# Sheet1.net
KiCad netlist of a schematic drawn in Altium Designer
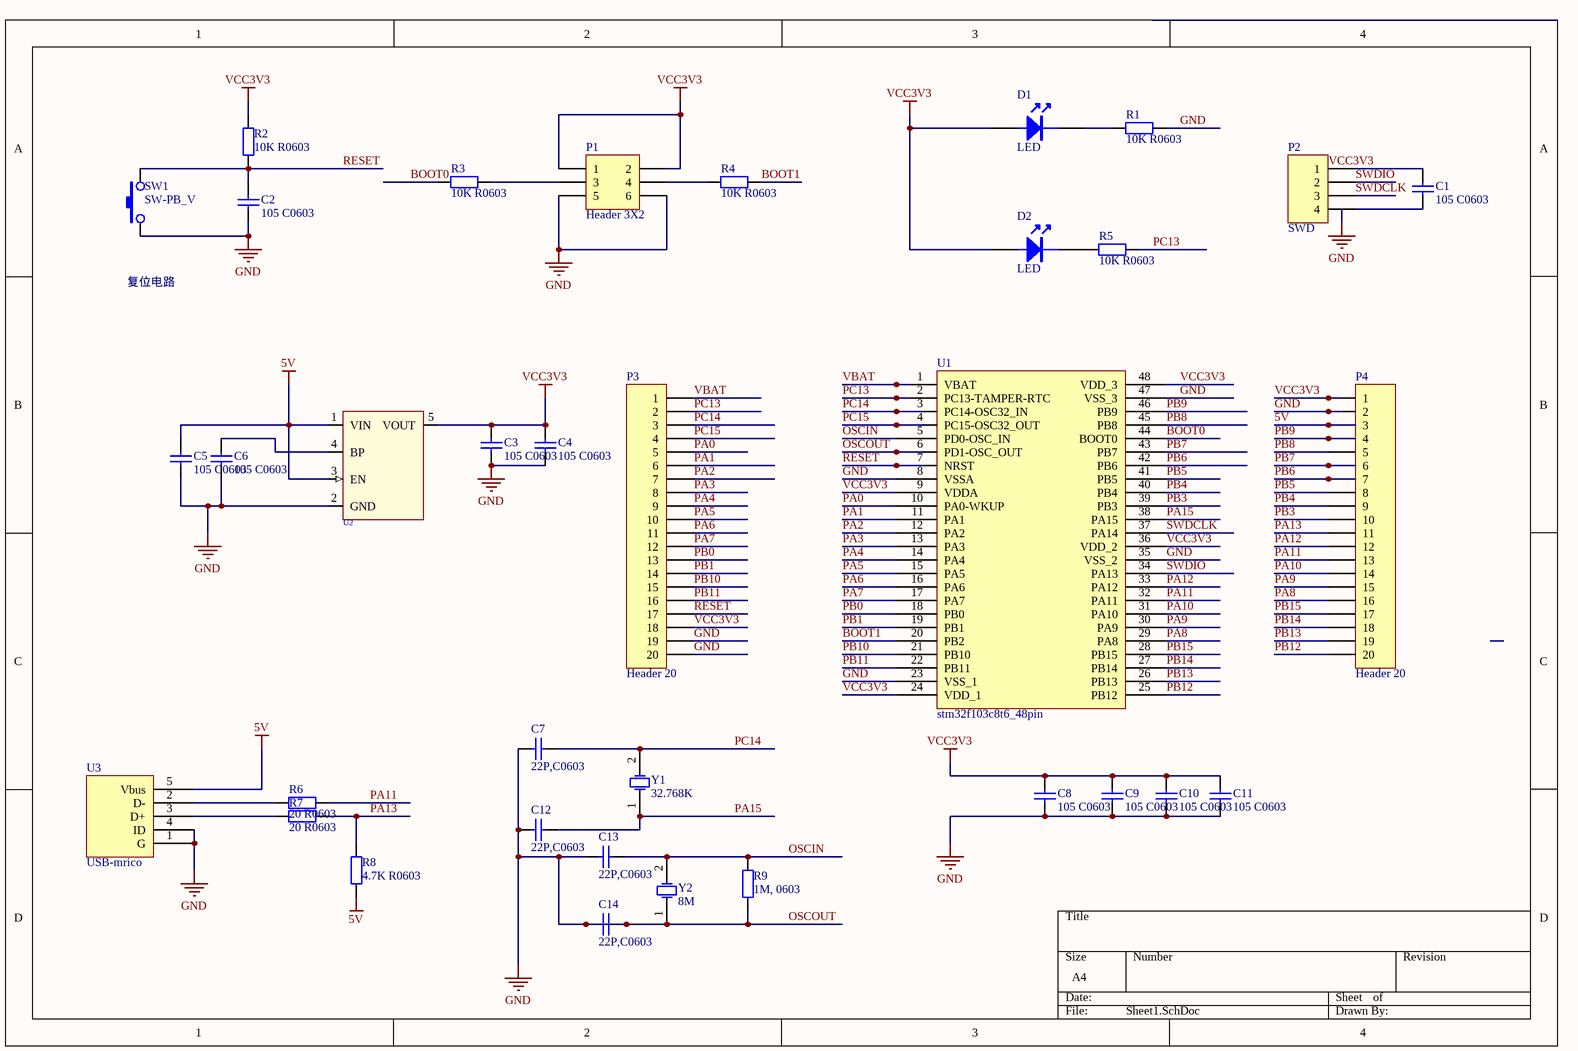
[diagram p0: Sheet1.SchDoc]

(export (version "E")
  (design (tool "Eeschema 10.0.6"))
  (components
    (comp (ref "C1")
      (value "105 C0603")
      (footprint "C 0603")
      (fields (field (name "PUBLISHER") "Altium Limited"))
      (libsource (lib "stm32原理图库") (part "Cap"))
    )
    (comp (ref "C2")
      (value "105 C0603")
      (footprint "C 0603")
      (fields (field (name "PUBLISHER") "Altium Limited"))
      (libsource (lib "stm32原理图库") (part "Cap"))
    )
    (comp (ref "C3")
      (value "105 C0603")
      (footprint "C 0603")
      (fields (field (name "PUBLISHER") "Altium Limited"))
      (libsource (lib "stm32原理图库") (part "Cap"))
    )
    (comp (ref "C4")
      (value "105 C0603")
      (footprint "C 0603")
      (fields (field (name "PUBLISHER") "Altium Limited"))
      (libsource (lib "stm32原理图库") (part "Cap"))
    )
    (comp (ref "C5")
      (value "105 C0603")
      (footprint "C 0603")
      (fields (field (name "PUBLISHER") "Altium Limited"))
      (libsource (lib "stm32原理图库") (part "Cap"))
    )
    (comp (ref "C6")
      (value "105 C0603")
      (footprint "C 0603")
      (fields (field (name "PUBLISHER") "Altium Limited"))
      (libsource (lib "stm32原理图库") (part "Cap"))
    )
    (comp (ref "C7")
      (value "22P,C0603")
      (footprint "C 0603")
      (fields (field (name "PUBLISHER") "Altium Limited"))
      (libsource (lib "stm32原理图库") (part "Cap"))
    )
    (comp (ref "C8")
      (value "105 C0603")
      (footprint "C 0603")
      (fields (field (name "PUBLISHER") "Altium Limited"))
      (libsource (lib "stm32原理图库") (part "Cap"))
    )
    (comp (ref "C9")
      (value "105 C0603")
      (footprint "C 0603")
      (fields (field (name "PUBLISHER") "Altium Limited"))
      (libsource (lib "stm32原理图库") (part "Cap"))
    )
    (comp (ref "C10")
      (value "105 C0603")
      (footprint "C 0603")
      (fields (field (name "PUBLISHER") "Altium Limited"))
      (libsource (lib "stm32原理图库") (part "Cap"))
    )
    (comp (ref "C11")
      (value "105 C0603")
      (footprint "C 0603")
      (fields (field (name "PUBLISHER") "Altium Limited"))
      (libsource (lib "stm32原理图库") (part "Cap"))
    )
    (comp (ref "C12")
      (value "22P,C0603")
      (footprint "C 0603")
      (fields (field (name "PUBLISHER") "Altium Limited"))
      (libsource (lib "stm32原理图库") (part "Cap"))
    )
    (comp (ref "C13")
      (value "22P,C0603")
      (footprint "C 0603")
      (fields (field (name "PUBLISHER") "Altium Limited"))
      (libsource (lib "stm32原理图库") (part "Cap"))
    )
    (comp (ref "C14")
      (value "22P,C0603")
      (footprint "C 0603")
      (fields (field (name "PUBLISHER") "Altium Limited"))
      (libsource (lib "stm32原理图库") (part "Cap"))
    )
    (comp (ref "D1") (value "LED") (footprint "LED 0805G") (libsource (lib "stm32原理图库") (part "LED")))
    (comp (ref "D2") (value "LED") (footprint "LED 0805G") (libsource (lib "stm32原理图库") (part "LED")))
    (comp (ref "P1")
      (value "Header 3X2")
      (footprint "HDR-3X2")
      (fields (field (name "PUBLISHER") "Altium Limited"))
      (libsource (lib "stm32原理图库") (part "Header 2*3"))
    )
    (comp (ref "P2")
      (value "SWD")
      (footprint "HDR-1X4_H")
      (fields (field (name "PUBLISHER") "Altium Limited"))
      (libsource (lib "stm32原理图库") (part "Header 1*4"))
    )
    (comp (ref "P3")
      (value "Header 20")
      (footprint "HDR1X20")
      (fields (field (name "PUBLISHER") "Altium Limited"))
      (libsource (lib "") (part "Header1* 20_1"))
    )
    (comp (ref "P4")
      (value "Header 20")
      (footprint "HDR1X20")
      (fields (field (name "PUBLISHER") "Altium Limited"))
      (libsource (lib "stm32原理图库") (part "Header1* 20"))
    )
    (comp (ref "R1")
      (value "10K R0603")
      (footprint "R 0603")
      (fields (field (name "PUBLISHER") "Altium Limited"))
      (libsource (lib "") (part "Res2_3"))
    )
    (comp (ref "R2")
      (value "10K R0603")
      (footprint "R 0603")
      (fields (field (name "PUBLISHER") "Altium Limited"))
      (libsource (lib "") (part "Res2_2"))
    )
    (comp (ref "R3")
      (value "10K R0603")
      (footprint "R 0603")
      (fields (field (name "PUBLISHER") "Altium Limited"))
      (libsource (lib "stm32原理图库") (part "Res2"))
    )
    (comp (ref "R4")
      (value "10K R0603")
      (footprint "R 0603")
      (fields (field (name "PUBLISHER") "Altium Limited"))
      (libsource (lib "stm32原理图库") (part "Res2"))
    )
    (comp (ref "R5")
      (value "10K R0603")
      (footprint "R 0603")
      (fields (field (name "PUBLISHER") "Altium Limited"))
      (libsource (lib "") (part "Res2_3"))
    )
    (comp (ref "R6")
      (value "20 R0603")
      (footprint "R 0603")
      (fields (field (name "PUBLISHER") "Altium Limited"))
      (libsource (lib "stm32原理图库") (part "Res2"))
    )
    (comp (ref "R7")
      (value "20 R0603")
      (footprint "R 0603")
      (fields (field (name "PUBLISHER") "Altium Limited"))
      (libsource (lib "stm32原理图库") (part "Res2"))
    )
    (comp (ref "R8")
      (value "4.7K R0603")
      (footprint "R 0603")
      (fields (field (name "PUBLISHER") "Altium Limited"))
      (libsource (lib "") (part "Res2_1"))
    )
    (comp (ref "R9")
      (value "1M, 0603")
      (footprint "R 0603")
      (fields (field (name "PUBLISHER") "Altium Limited"))
      (libsource (lib "") (part "Res2_1"))
    )
    (comp (ref "SW1")
      (value "SW-PB_V")
      (footprint "TSW SMD-3*6*2.5")
      (libsource (lib "stm32原理图库") (part "SW-PB_V"))
    )
    (comp (ref "U1")
      (value "stm32f103c8t6_48pin")
      (footprint "TQFP48 7x7_L")
      (libsource (lib "stm32原理图库") (part "stm32f103c8t6_48pin"))
    )
    (comp (ref "U2")
      (value "RT9193")
      (footprint "SOT23-5L")
      (fields (field (name "ICA_PARTNUM") "$$2191094$$RT9193-15CU5") (field (name "PART NUMBER") "TMP-13"))
      (libsource (lib "stm32原理图库") (part "RT9193X_5P"))
    )
    (comp (ref "U3")
      (value "USB-mrico")
      (footprint "USB-micro_B")
      (libsource (lib "stm32原理图库") (part "usb-STM"))
    )
    (comp (ref "Y1")
      (value "32.768K")
      (footprint "XTAL-49S DIP")
      (fields (field (name "PUBLISHER") "Altium Limited"))
      (libsource (lib "stm32原理图库") (part "XTAL"))
    )
    (comp (ref "Y2")
      (value "8M")
      (footprint "XTAL-49S DIP")
      (fields (field (name "PUBLISHER") "Altium Limited"))
      (libsource (lib "stm32原理图库") (part "XTAL"))
    )
  )
  (nets
    (net (code "1") (name "/BOOT0") (class "Default")
      (node (ref "R3") (pin "2") (pinfunction "2_2") (pintype "passive"))
      (node (ref "U1") (pin "44") (pinfunction "BOOT0_44") (pintype "passive"))
    )
    (net (code "2") (name "/BOOT1") (class "Default")
      (node (ref "R4") (pin "1") (pinfunction "1_1") (pintype "passive"))
      (node (ref "U1") (pin "20") (pinfunction "PB2_20") (pintype "passive"))
    )
    (net (code "3") (name "/OSCIN") (class "Default")
      (node (ref "C13") (pin "1") (pinfunction "1_1") (pintype "passive"))
      (node (ref "R9") (pin "1") (pinfunction "1_1") (pintype "passive"))
      (node (ref "U1") (pin "5") (pinfunction "PD0-OSC_IN_5") (pintype "passive"))
      (node (ref "Y2") (pin "2") (pinfunction "OSC2_2") (pintype "passive"))
    )
    (net (code "4") (name "/PA0") (class "Default")
      (node (ref "P3") (pin "5") (pinfunction "5_5") (pintype "passive"))
      (node (ref "U1") (pin "10") (pinfunction "PA0-WKUP_10") (pintype "passive"))
    )
    (net (code "5") (name "/PA1") (class "Default")
      (node (ref "P3") (pin "6") (pinfunction "6_6") (pintype "passive"))
      (node (ref "U1") (pin "11") (pinfunction "PA1_11") (pintype "passive"))
    )
    (net (code "6") (name "/PA2") (class "Default")
      (node (ref "P3") (pin "7") (pinfunction "7_7") (pintype "passive"))
      (node (ref "U1") (pin "12") (pinfunction "PA2_12") (pintype "passive"))
    )
    (net (code "7") (name "/PA3") (class "Default")
      (node (ref "P3") (pin "8") (pinfunction "8_8") (pintype "passive"))
      (node (ref "U1") (pin "13") (pinfunction "PA3_13") (pintype "passive"))
    )
    (net (code "8") (name "/PA4") (class "Default")
      (node (ref "P3") (pin "9") (pinfunction "9_9") (pintype "passive"))
      (node (ref "U1") (pin "14") (pinfunction "PA4_14") (pintype "passive"))
    )
    (net (code "9") (name "/PA5") (class "Default")
      (node (ref "P3") (pin "10") (pinfunction "10_10") (pintype "passive"))
      (node (ref "U1") (pin "15") (pinfunction "PA5_15") (pintype "passive"))
    )
    (net (code "10") (name "/PA6") (class "Default")
      (node (ref "P3") (pin "11") (pinfunction "11_11") (pintype "passive"))
      (node (ref "U1") (pin "16") (pinfunction "PA6_16") (pintype "passive"))
    )
    (net (code "11") (name "/PA7") (class "Default")
      (node (ref "P3") (pin "12") (pinfunction "12_12") (pintype "passive"))
      (node (ref "U1") (pin "17") (pinfunction "PA7_17") (pintype "passive"))
    )
    (net (code "12") (name "/PA8") (class "Default")
      (node (ref "P4") (pin "16") (pinfunction "16_16") (pintype "passive"))
      (node (ref "U1") (pin "29") (pinfunction "PA8_29") (pintype "passive"))
    )
    (net (code "13") (name "/PA9") (class "Default")
      (node (ref "P4") (pin "15") (pinfunction "15_15") (pintype "passive"))
      (node (ref "U1") (pin "30") (pinfunction "PA9_30") (pintype "passive"))
    )
    (net (code "14") (name "/PA10") (class "Default")
      (node (ref "P4") (pin "14") (pinfunction "14_14") (pintype "passive"))
      (node (ref "U1") (pin "31") (pinfunction "PA10_31") (pintype "passive"))
    )
    (net (code "15") (name "/PA11") (class "Default")
      (node (ref "P4") (pin "13") (pinfunction "13_13") (pintype "passive"))
      (node (ref "R6") (pin "1") (pinfunction "1_1") (pintype "passive"))
      (node (ref "U1") (pin "32") (pinfunction "PA11_32") (pintype "passive"))
    )
    (net (code "16") (name "/PA12") (class "Default")
      (node (ref "P4") (pin "12") (pinfunction "12_12") (pintype "passive"))
      (node (ref "U1") (pin "33") (pinfunction "PA12_33") (pintype "passive"))
    )
    (net (code "17") (name "/PA13") (class "Default")
      (node (ref "P4") (pin "11") (pinfunction "11_11") (pintype "passive"))
      (node (ref "R7") (pin "1") (pinfunction "1_1") (pintype "passive"))
      (node (ref "R8") (pin "1") (pinfunction "1_1") (pintype "passive"))
    )
    (net (code "18") (name "/PA15") (class "Default")
      (node (ref "C12") (pin "1") (pinfunction "1_1") (pintype "passive"))
      (node (ref "U1") (pin "38") (pinfunction "PA15_38") (pintype "passive"))
      (node (ref "Y1") (pin "1") (pinfunction "OSC1_1") (pintype "passive"))
    )
    (net (code "19") (name "/PB0") (class "Default")
      (node (ref "P3") (pin "13") (pinfunction "13_13") (pintype "passive"))
      (node (ref "U1") (pin "18") (pinfunction "PB0_18") (pintype "passive"))
    )
    (net (code "20") (name "/PB1") (class "Default")
      (node (ref "P3") (pin "14") (pinfunction "14_14") (pintype "passive"))
      (node (ref "U1") (pin "19") (pinfunction "PB1_19") (pintype "passive"))
    )
    (net (code "21") (name "/PB3") (class "Default")
      (node (ref "P4") (pin "10") (pinfunction "10_10") (pintype "passive"))
      (node (ref "U1") (pin "39") (pinfunction "PB3_39") (pintype "passive"))
    )
    (net (code "22") (name "/PB4") (class "Default")
      (node (ref "P4") (pin "9") (pinfunction "9_9") (pintype "passive"))
      (node (ref "U1") (pin "40") (pinfunction "PB4_40") (pintype "passive"))
    )
    (net (code "23") (name "/PB5") (class "Default")
      (node (ref "P4") (pin "8") (pinfunction "8_8") (pintype "passive"))
      (node (ref "U1") (pin "41") (pinfunction "PB5_41") (pintype "passive"))
    )
    (net (code "24") (name "/PB6") (class "Default")
      (node (ref "P4") (pin "7") (pinfunction "7_7") (pintype "passive"))
      (node (ref "U1") (pin "42") (pinfunction "PB6_42") (pintype "passive"))
    )
    (net (code "25") (name "/PB7") (class "Default")
      (node (ref "P4") (pin "6") (pinfunction "6_6") (pintype "passive"))
      (node (ref "U1") (pin "43") (pinfunction "PB7_43") (pintype "passive"))
    )
    (net (code "26") (name "/PB8") (class "Default")
      (node (ref "P4") (pin "5") (pinfunction "5_5") (pintype "passive"))
      (node (ref "U1") (pin "45") (pinfunction "PB8_45") (pintype "passive"))
    )
    (net (code "27") (name "/PB9") (class "Default")
      (node (ref "P4") (pin "4") (pinfunction "4_4") (pintype "passive"))
      (node (ref "U1") (pin "46") (pinfunction "PB9_46") (pintype "passive"))
    )
    (net (code "28") (name "/PB10") (class "Default")
      (node (ref "P3") (pin "15") (pinfunction "15_15") (pintype "passive"))
      (node (ref "U1") (pin "21") (pinfunction "PB10_21") (pintype "passive"))
    )
    (net (code "29") (name "/PB11") (class "Default")
      (node (ref "P3") (pin "16") (pinfunction "16_16") (pintype "passive"))
      (node (ref "U1") (pin "22") (pinfunction "PB11_22") (pintype "passive"))
    )
    (net (code "30") (name "/PB12") (class "Default")
      (node (ref "P4") (pin "20") (pinfunction "20_20") (pintype "passive"))
      (node (ref "U1") (pin "25") (pinfunction "PB12_25") (pintype "passive"))
    )
    (net (code "31") (name "/PB13") (class "Default")
      (node (ref "P4") (pin "19") (pinfunction "19_19") (pintype "passive"))
      (node (ref "U1") (pin "26") (pinfunction "PB13_26") (pintype "passive"))
    )
    (net (code "32") (name "/PB14") (class "Default")
      (node (ref "P4") (pin "18") (pinfunction "18_18") (pintype "passive"))
      (node (ref "U1") (pin "27") (pinfunction "PB14_27") (pintype "passive"))
    )
    (net (code "33") (name "/PB15") (class "Default")
      (node (ref "P4") (pin "17") (pinfunction "17_17") (pintype "passive"))
      (node (ref "U1") (pin "28") (pinfunction "PB15_28") (pintype "passive"))
    )
    (net (code "34") (name "/PC13") (class "Default")
      (node (ref "P3") (pin "2") (pinfunction "2_2") (pintype "passive"))
      (node (ref "R5") (pin "2") (pinfunction "2_2") (pintype "passive"))
      (node (ref "U1") (pin "2") (pinfunction "PC13-TAMPER-RTC_2") (pintype "passive"))
    )
    (net (code "35") (name "/PC14") (class "Default")
      (node (ref "C7") (pin "1") (pinfunction "1_1") (pintype "passive"))
      (node (ref "P3") (pin "3") (pinfunction "3_3") (pintype "passive"))
      (node (ref "U1") (pin "3") (pinfunction "PC14-OSC32_IN_3") (pintype "passive"))
      (node (ref "Y1") (pin "2") (pinfunction "OSC2_2") (pintype "passive"))
    )
    (net (code "36") (name "/PC15") (class "Default")
      (node (ref "P3") (pin "4") (pinfunction "4_4") (pintype "passive"))
      (node (ref "U1") (pin "4") (pinfunction "PC15-OSC32_OUT_4") (pintype "passive"))
    )
    (net (code "37") (name "/RESET") (class "Default")
      (node (ref "C2") (pin "2") (pinfunction "2_2") (pintype "passive"))
      (node (ref "P3") (pin "17") (pinfunction "17_17") (pintype "passive"))
      (node (ref "R2") (pin "1") (pinfunction "1_1") (pintype "passive"))
      (node (ref "SW1") (pin "2") (pinfunction "2_2") (pintype "passive"))
      (node (ref "U1") (pin "7") (pinfunction "NRST_7") (pintype "passive"))
    )
    (net (code "38") (name "/SWDCLK") (class "Default")
      (node (ref "P2") (pin "3") (pinfunction "3_3") (pintype "passive"))
      (node (ref "U1") (pin "37") (pinfunction "PA14_37") (pintype "passive"))
    )
    (net (code "39") (name "/SWDIO") (class "Default")
      (node (ref "P2") (pin "2") (pinfunction "2_2") (pintype "passive"))
      (node (ref "U1") (pin "34") (pinfunction "PA13_34") (pintype "passive"))
    )
    (net (code "40") (name "/VBAT") (class "Default")
      (node (ref "P3") (pin "1") (pinfunction "1_1") (pintype "passive"))
      (node (ref "U1") (pin "1") (pinfunction "VBAT_1") (pintype "passive"))
    )
    (net (code "41") (name "5V") (class "Default")
      (node (ref "C5") (pin "2") (pinfunction "2_2") (pintype "passive"))
      (node (ref "P4") (pin "3") (pinfunction "3_3") (pintype "passive"))
      (node (ref "R8") (pin "2") (pinfunction "2_2") (pintype "passive"))
      (node (ref "U2") (pin "1") (pinfunction "VIN_1") (pintype "power_in"))
      (node (ref "U2") (pin "3") (pinfunction "EN_3") (pintype "input"))
      (node (ref "U3") (pin "5") (pinfunction "Vbus_5") (pintype "passive"))
    )
    (net (code "42") (name "GND") (class "Default")
      (node (ref "C10") (pin "1") (pinfunction "1_1") (pintype "passive"))
      (node (ref "C11") (pin "1") (pinfunction "1_1") (pintype "passive"))
      (node (ref "C12") (pin "2") (pinfunction "2_2") (pintype "passive"))
      (node (ref "C13") (pin "2") (pinfunction "2_2") (pintype "passive"))
      (node (ref "C14") (pin "1") (pinfunction "1_1") (pintype "passive"))
      (node (ref "C14") (pin "2") (pinfunction "2_2") (pintype "passive"))
      (node (ref "C2") (pin "1") (pinfunction "1_1") (pintype "passive"))
      (node (ref "C3") (pin "1") (pinfunction "1_1") (pintype "passive"))
      (node (ref "C4") (pin "1") (pinfunction "1_1") (pintype "passive"))
      (node (ref "C5") (pin "1") (pinfunction "1_1") (pintype "passive"))
      (node (ref "C6") (pin "1") (pinfunction "1_1") (pintype "passive"))
      (node (ref "C7") (pin "2") (pinfunction "2_2") (pintype "passive"))
      (node (ref "C8") (pin "1") (pinfunction "1_1") (pintype "passive"))
      (node (ref "C9") (pin "1") (pinfunction "1_1") (pintype "passive"))
      (node (ref "P1") (pin "5") (pinfunction "5_5") (pintype "passive"))
      (node (ref "P1") (pin "6") (pinfunction "6_6") (pintype "passive"))
      (node (ref "P3") (pin "19") (pinfunction "19_19") (pintype "passive"))
      (node (ref "P3") (pin "20") (pinfunction "20_20") (pintype "passive"))
      (node (ref "P4") (pin "2") (pinfunction "2_2") (pintype "passive"))
      (node (ref "R1") (pin "2") (pinfunction "2_2") (pintype "passive"))
      (node (ref "R9") (pin "2") (pinfunction "2_2") (pintype "passive"))
      (node (ref "SW1") (pin "1") (pinfunction "1_1") (pintype "passive"))
      (node (ref "U1") (pin "23") (pinfunction "VSS_1_23") (pintype "passive"))
      (node (ref "U1") (pin "35") (pinfunction "VSS_2_35") (pintype "passive"))
      (node (ref "U1") (pin "47") (pinfunction "VSS_3_47") (pintype "passive"))
      (node (ref "U1") (pin "6") (pinfunction "PD1-OSC_OUT_6") (pintype "passive"))
      (node (ref "U1") (pin "8") (pinfunction "VSSA_8") (pintype "passive"))
      (node (ref "U2") (pin "2") (pinfunction "GND_2") (pintype "power_in"))
      (node (ref "U3") (pin "1") (pinfunction "G_1") (pintype "passive"))
      (node (ref "U3") (pin "4") (pinfunction "ID_4") (pintype "passive"))
      (node (ref "Y2") (pin "1") (pinfunction "OSC1_1") (pintype "passive"))
    )
    (net (code "43") (name "Net-(C1-Pad1)") (class "Default")
      (node (ref "C1") (pin "1") (pinfunction "1_1") (pintype "passive"))
      (node (ref "P2") (pin "4") (pinfunction "4_4") (pintype "passive"))
    )
    (net (code "44") (name "Net-(C1-Pad2)") (class "Default")
      (node (ref "C1") (pin "2") (pinfunction "2_2") (pintype "passive"))
      (node (ref "P2") (pin "1") (pinfunction "1_1") (pintype "passive"))
    )
    (net (code "45") (name "Net-(D1-Pad2)") (class "Default")
      (node (ref "D1") (pin "2") (pinfunction "2_2") (pintype "passive"))
      (node (ref "R1") (pin "1") (pinfunction "1_1") (pintype "passive"))
    )
    (net (code "46") (name "Net-(D2-Pad2)") (class "Default")
      (node (ref "D2") (pin "2") (pinfunction "2_2") (pintype "passive"))
      (node (ref "R5") (pin "1") (pinfunction "1_1") (pintype "passive"))
    )
    (net (code "47") (name "Net-(P1-Pad3)") (class "Default")
      (node (ref "P1") (pin "3") (pinfunction "3_3") (pintype "passive"))
      (node (ref "R3") (pin "1") (pinfunction "1_1") (pintype "passive"))
    )
    (net (code "48") (name "Net-(P1-Pad4)") (class "Default")
      (node (ref "P1") (pin "4") (pinfunction "4_4") (pintype "passive"))
      (node (ref "R4") (pin "2") (pinfunction "2_2") (pintype "passive"))
    )
    (net (code "49") (name "Net-(U2-BP)") (class "Default")
      (node (ref "C6") (pin "2") (pinfunction "2_2") (pintype "passive"))
      (node (ref "U2") (pin "4") (pinfunction "BP_4") (pintype "passive"))
    )
    (net (code "50") (name "Net-(U3-D+)") (class "Default")
      (node (ref "R7") (pin "2") (pinfunction "2_2") (pintype "passive"))
      (node (ref "U3") (pin "3") (pinfunction "D+_3") (pintype "passive"))
    )
    (net (code "51") (name "Net-(U3-D-)") (class "Default")
      (node (ref "R6") (pin "2") (pinfunction "2_2") (pintype "passive"))
      (node (ref "U3") (pin "2") (pinfunction "D-_2") (pintype "passive"))
    )
    (net (code "52") (name "VCC3V3") (class "Default")
      (node (ref "C10") (pin "2") (pinfunction "2_2") (pintype "passive"))
      (node (ref "C11") (pin "2") (pinfunction "2_2") (pintype "passive"))
      (node (ref "C3") (pin "2") (pinfunction "2_2") (pintype "passive"))
      (node (ref "C4") (pin "2") (pinfunction "2_2") (pintype "passive"))
      (node (ref "C8") (pin "2") (pinfunction "2_2") (pintype "passive"))
      (node (ref "C9") (pin "2") (pinfunction "2_2") (pintype "passive"))
      (node (ref "D1") (pin "1") (pinfunction "1_1") (pintype "passive"))
      (node (ref "D2") (pin "1") (pinfunction "1_1") (pintype "passive"))
      (node (ref "P1") (pin "1") (pinfunction "1_1") (pintype "passive"))
      (node (ref "P1") (pin "2") (pinfunction "2_2") (pintype "passive"))
      (node (ref "P3") (pin "18") (pinfunction "18_18") (pintype "passive"))
      (node (ref "P4") (pin "1") (pinfunction "1_1") (pintype "passive"))
      (node (ref "R2") (pin "2") (pinfunction "2_2") (pintype "passive"))
      (node (ref "U1") (pin "24") (pinfunction "VDD_1_24") (pintype "passive"))
      (node (ref "U1") (pin "36") (pinfunction "VDD_2_36") (pintype "passive"))
      (node (ref "U1") (pin "48") (pinfunction "VDD_3_48") (pintype "passive"))
      (node (ref "U1") (pin "9") (pinfunction "VDDA_9") (pintype "passive"))
      (node (ref "U2") (pin "5") (pinfunction "VOUT_5") (pintype "power_in"))
    )
  )
)
